# LEDS-SMD.net
KiCad netlist of a schematic drawn in Altium Designer
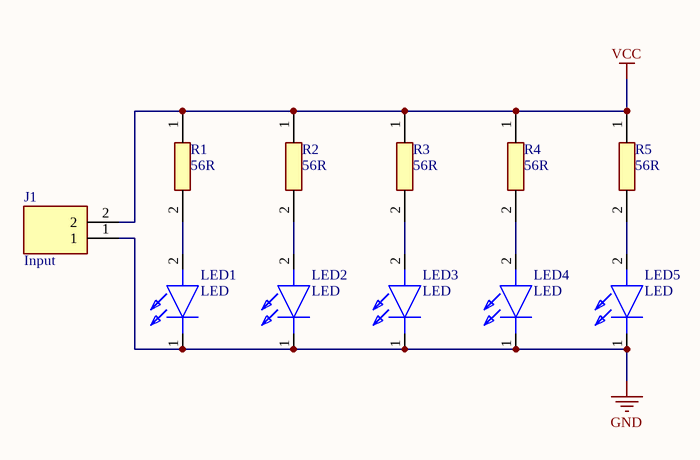
[diagram p0: LEDS-SMD.SchDoc]

(export (version "E")
  (design (tool "Eeschema 10.0.6"))
  (components
    (comp (ref "J1")
      (value "Input")
      (footprint "SamacSys:1760510000")
      (description "Connector")
      (fields
        (field (name "MANUFACTURER_PART_NUMBER") "1760510000")
        (field (name "MOUSER PART NUMBER") "470-1760510000")
      )
      (libsource (lib "*") (part "1760510000"))
    )
    (comp (ref "LED1")
      (value "LED")
      (footprint "SamacSys:LEDC2012X90N")
      (fields
        (field (name "MANUFACTURER_PART_NUMBER") "HSML-C170-T0000")
        (field (name "MOUSER PART NUMBER") "630-HSML-C170-T0000")
      )
      (libsource (lib "*") (part "HSML-C170-T0000"))
    )
    (comp (ref "LED2")
      (value "LED")
      (footprint "SamacSys:LEDC2012X90N")
      (fields
        (field (name "MANUFACTURER_PART_NUMBER") "HSML-C170-T0000")
        (field (name "MOUSER PART NUMBER") "630-HSML-C170-T0000")
      )
      (libsource (lib "*") (part "HSML-C170-T0000"))
    )
    (comp (ref "LED3")
      (value "LED")
      (footprint "SamacSys:LEDC2012X90N")
      (fields
        (field (name "MANUFACTURER_PART_NUMBER") "HSML-C170-T0000")
        (field (name "MOUSER PART NUMBER") "630-HSML-C170-T0000")
      )
      (libsource (lib "*") (part "HSML-C170-T0000"))
    )
    (comp (ref "LED4")
      (value "LED")
      (footprint "SamacSys:LEDC2012X90N")
      (fields
        (field (name "MANUFACTURER_PART_NUMBER") "HSML-C170-T0000")
        (field (name "MOUSER PART NUMBER") "630-HSML-C170-T0000")
      )
      (libsource (lib "*") (part "HSML-C170-T0000"))
    )
    (comp (ref "LED5")
      (value "LED")
      (footprint "SamacSys:LEDC2012X90N")
      (fields
        (field (name "MANUFACTURER_PART_NUMBER") "HSML-C170-T0000")
        (field (name "MOUSER PART NUMBER") "630-HSML-C170-T0000")
      )
      (libsource (lib "*") (part "HSML-C170-T0000"))
    )
    (comp (ref "R1")
      (value "56R")
      (footprint "SamacSys:RESC2012X50N")
      (description "Resistor")
      (fields
        (field (name "MANUFACTURER_PART_NUMBER") "CRCW080556R0FKEA")
        (field (name "MOUSER PART NUMBER") "71-CRCW080556R0FKEA")
      )
      (libsource (lib "*") (part "CRCW080556R0FKEA"))
    )
    (comp (ref "R2")
      (value "56R")
      (footprint "SamacSys:RESC2012X50N")
      (description "Resistor")
      (fields
        (field (name "MANUFACTURER_PART_NUMBER") "CRCW080556R0FKEA")
        (field (name "MOUSER PART NUMBER") "71-CRCW080556R0FKEA")
      )
      (libsource (lib "*") (part "CRCW080556R0FKEA"))
    )
    (comp (ref "R3")
      (value "56R")
      (footprint "SamacSys:RESC2012X50N")
      (description "Resistor")
      (fields
        (field (name "MANUFACTURER_PART_NUMBER") "CRCW080556R0FKEA")
        (field (name "MOUSER PART NUMBER") "71-CRCW080556R0FKEA")
      )
      (libsource (lib "*") (part "CRCW080556R0FKEA"))
    )
    (comp (ref "R4")
      (value "56R")
      (footprint "SamacSys:RESC2012X50N")
      (description "Resistor")
      (fields
        (field (name "MANUFACTURER_PART_NUMBER") "CRCW080556R0FKEA")
        (field (name "MOUSER PART NUMBER") "71-CRCW080556R0FKEA")
      )
      (libsource (lib "*") (part "CRCW080556R0FKEA"))
    )
    (comp (ref "R5")
      (value "56R")
      (footprint "SamacSys:RESC2012X50N")
      (description "Resistor")
      (fields
        (field (name "MANUFACTURER_PART_NUMBER") "CRCW080556R0FKEA")
        (field (name "MOUSER PART NUMBER") "71-CRCW080556R0FKEA")
      )
      (libsource (lib "*") (part "CRCW080556R0FKEA"))
    )
  )
  (nets
    (net (code "1") (name "GND") (class "Default")
      (node (ref "J1") (pin "1") (pinfunction "1_1") (pintype "passive"))
      (node (ref "LED1") (pin "1") (pinfunction "K_1") (pintype "passive"))
      (node (ref "LED2") (pin "1") (pinfunction "K_1") (pintype "passive"))
      (node (ref "LED3") (pin "1") (pinfunction "K_1") (pintype "passive"))
      (node (ref "LED4") (pin "1") (pinfunction "K_1") (pintype "passive"))
      (node (ref "LED5") (pin "1") (pinfunction "K_1") (pintype "passive"))
    )
    (net (code "2") (name "Net-(LED1-A)") (class "Default")
      (node (ref "LED1") (pin "2") (pinfunction "A_2") (pintype "passive"))
      (node (ref "R1") (pin "2") (pinfunction "2_2") (pintype "passive"))
    )
    (net (code "3") (name "Net-(LED2-A)") (class "Default")
      (node (ref "LED2") (pin "2") (pinfunction "A_2") (pintype "passive"))
      (node (ref "R2") (pin "2") (pinfunction "2_2") (pintype "passive"))
    )
    (net (code "4") (name "Net-(LED3-A)") (class "Default")
      (node (ref "LED3") (pin "2") (pinfunction "A_2") (pintype "passive"))
      (node (ref "R3") (pin "2") (pinfunction "2_2") (pintype "passive"))
    )
    (net (code "5") (name "Net-(LED4-A)") (class "Default")
      (node (ref "LED4") (pin "2") (pinfunction "A_2") (pintype "passive"))
      (node (ref "R4") (pin "2") (pinfunction "2_2") (pintype "passive"))
    )
    (net (code "6") (name "Net-(LED5-A)") (class "Default")
      (node (ref "LED5") (pin "2") (pinfunction "A_2") (pintype "passive"))
      (node (ref "R5") (pin "2") (pinfunction "2_2") (pintype "passive"))
    )
    (net (code "7") (name "VCC") (class "Default")
      (node (ref "J1") (pin "2") (pinfunction "2_2") (pintype "passive"))
      (node (ref "R1") (pin "1") (pinfunction "1_1") (pintype "passive"))
      (node (ref "R2") (pin "1") (pinfunction "1_1") (pintype "passive"))
      (node (ref "R3") (pin "1") (pinfunction "1_1") (pintype "passive"))
      (node (ref "R4") (pin "1") (pinfunction "1_1") (pintype "passive"))
      (node (ref "R5") (pin "1") (pinfunction "1_1") (pintype "passive"))
    )
  )
)
